# connecteurs.net
KiCad netlist of a schematic drawn in Altium Designer
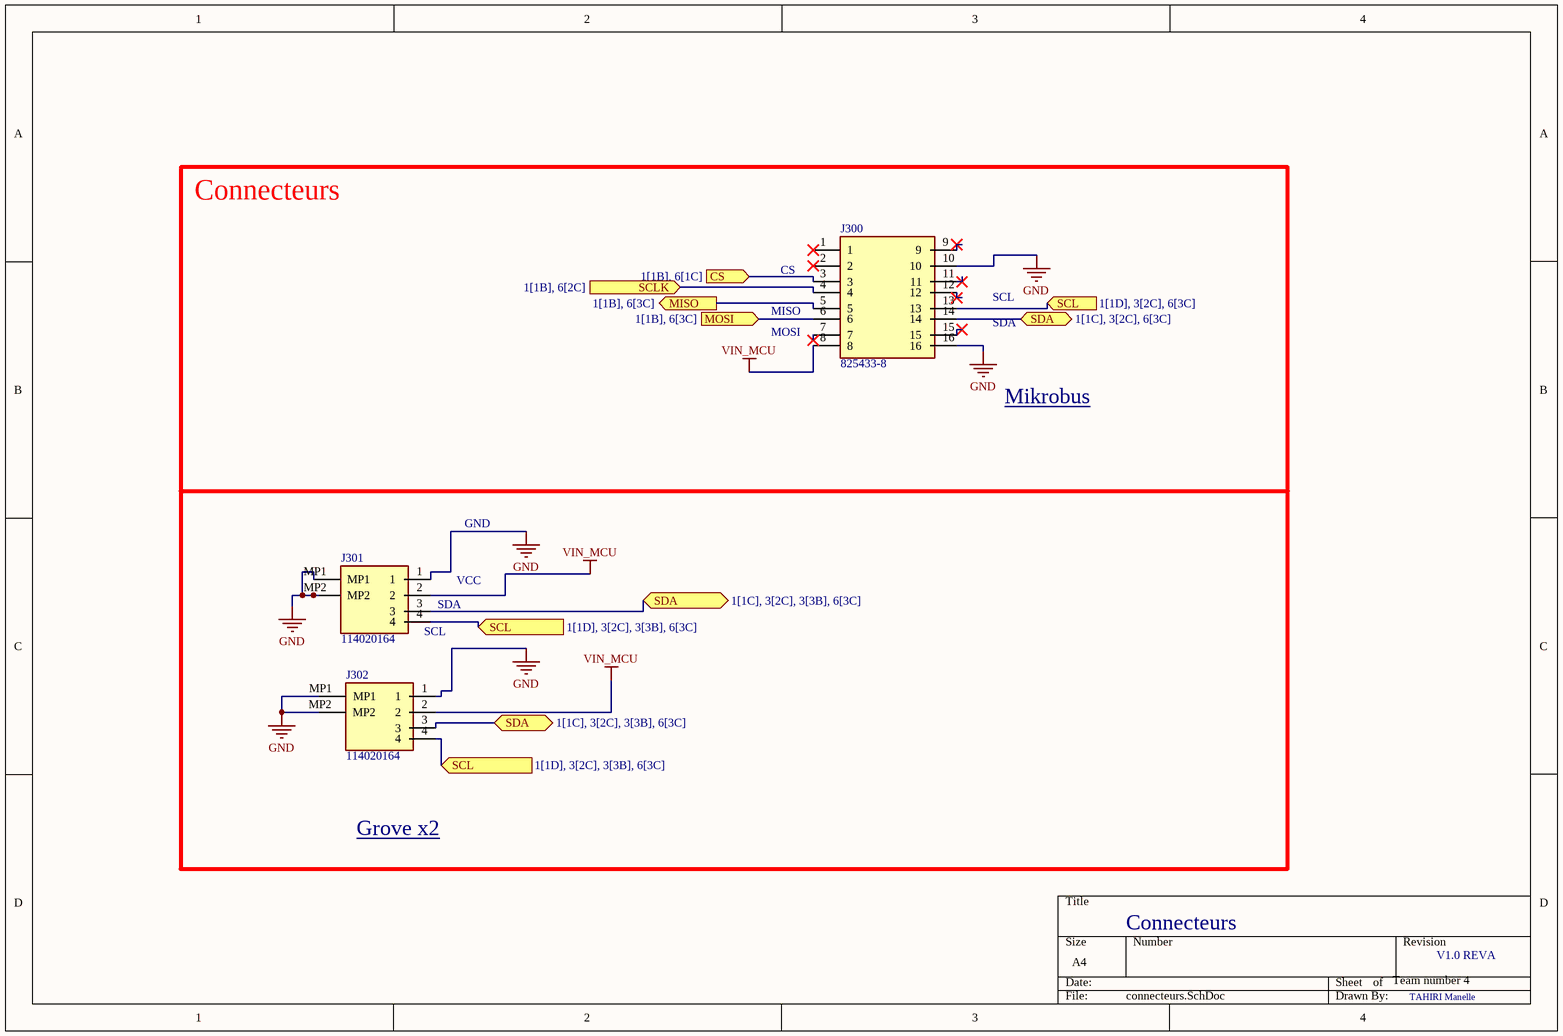
[diagram p0: connecteurs.SchDoc]

(export (version "E")
  (design (tool "Eeschema 10.0.6"))
  (components
    (comp (ref "J300")
      (value "825433-8")
      (description "Headers & Wire Housings 8P double for connection mikrobus")
      (fields (field (name "MOUSER PART NUMBER") "571-825433-8"))
      (libsource (lib "SCHLibrary") (part "Connect-Mikronus"))
    )
    (comp (ref "J301")
      (value "114020164")
      (footprint "114020164")
      (description "Seeed Studio Accessories Grove Female Header - SMD-4P-2.0mm-90D-20Pcs")
      (fields (field (name "MOUSER PART NUMBER") "713-114020164"))
      (libsource (lib "SCHLibrary") (part "114020164"))
    )
    (comp (ref "J302")
      (value "114020164")
      (footprint "114020164")
      (description "Seeed Studio Accessories Grove Female Header - SMD-4P-2.0mm-90D-20Pcs")
      (fields (field (name "MOUSER PART NUMBER") "713-114020164"))
      (libsource (lib "SCHLibrary") (part "114020164"))
    )
  )
  (nets
    (net (code "1") (name "/CS") (class "Default")
      (node (ref "J300") (pin "3") (pinfunction "3_3") (pintype "passive"))
    )
    (net (code "2") (name "/MISO") (class "Default")
      (node (ref "J300") (pin "5") (pinfunction "5_5") (pintype "passive"))
    )
    (net (code "3") (name "/MOSI") (class "Default")
      (node (ref "J300") (pin "6") (pinfunction "6_6") (pintype "passive"))
    )
    (net (code "4") (name "/SCL") (class "Default")
      (node (ref "J300") (pin "13") (pinfunction "13_13") (pintype "passive"))
      (node (ref "J301") (pin "4") (pinfunction "4_4") (pintype "passive"))
      (node (ref "J302") (pin "4") (pinfunction "4_4") (pintype "passive"))
    )
    (net (code "5") (name "/SCLK") (class "Default")
      (node (ref "J300") (pin "4") (pinfunction "4_4") (pintype "passive"))
    )
    (net (code "6") (name "/SDA") (class "Default")
      (node (ref "J300") (pin "14") (pinfunction "14_14") (pintype "passive"))
      (node (ref "J301") (pin "3") (pinfunction "3_3") (pintype "passive"))
      (node (ref "J302") (pin "3") (pinfunction "3_3") (pintype "passive"))
    )
    (net (code "7") (name "GND") (class "Default")
      (node (ref "J300") (pin "10") (pinfunction "10_10") (pintype "passive"))
      (node (ref "J300") (pin "16") (pinfunction "16_16") (pintype "passive"))
      (node (ref "J301") (pin "1") (pinfunction "1_1") (pintype "passive"))
      (node (ref "J301") (pin "MP1") (pinfunction "MP1_MP1") (pintype "passive"))
      (node (ref "J301") (pin "MP2") (pinfunction "MP2_MP2") (pintype "passive"))
      (node (ref "J302") (pin "1") (pinfunction "1_1") (pintype "passive"))
      (node (ref "J302") (pin "MP1") (pinfunction "MP1_MP1") (pintype "passive"))
      (node (ref "J302") (pin "MP2") (pinfunction "MP2_MP2") (pintype "passive"))
    )
    (net (code "8") (name "VIN_MCU") (class "Default")
      (node (ref "J300") (pin "8") (pinfunction "8_8") (pintype "passive"))
      (node (ref "J301") (pin "2") (pinfunction "2_2") (pintype "passive"))
      (node (ref "J302") (pin "2") (pinfunction "2_2") (pintype "passive"))
    )
    (net (code "9") (name "unconnected-(J300-Pad1)") (class "Default")
      (node (ref "J300") (pin "1") (pinfunction "1_1") (pintype "passive+no_connect"))
    )
    (net (code "10") (name "unconnected-(J300-Pad2)") (class "Default")
      (node (ref "J300") (pin "2") (pinfunction "2_2") (pintype "passive+no_connect"))
    )
    (net (code "11") (name "unconnected-(J300-Pad7)") (class "Default")
      (node (ref "J300") (pin "7") (pinfunction "7_7") (pintype "passive+no_connect"))
    )
    (net (code "12") (name "unconnected-(J300-Pad9)") (class "Default")
      (node (ref "J300") (pin "9") (pinfunction "9_9") (pintype "passive+no_connect"))
    )
    (net (code "13") (name "unconnected-(J300-Pad11)") (class "Default")
      (node (ref "J300") (pin "11") (pinfunction "11_11") (pintype "passive+no_connect"))
    )
    (net (code "14") (name "unconnected-(J300-Pad12)") (class "Default")
      (node (ref "J300") (pin "12") (pinfunction "12_12") (pintype "passive+no_connect"))
    )
    (net (code "15") (name "unconnected-(J300-Pad15)") (class "Default")
      (node (ref "J300") (pin "15") (pinfunction "15_15") (pintype "passive+no_connect"))
    )
  )
)
